# FMC_Test_Module.net
KiCad netlist of a schematic drawn in Altium Designer
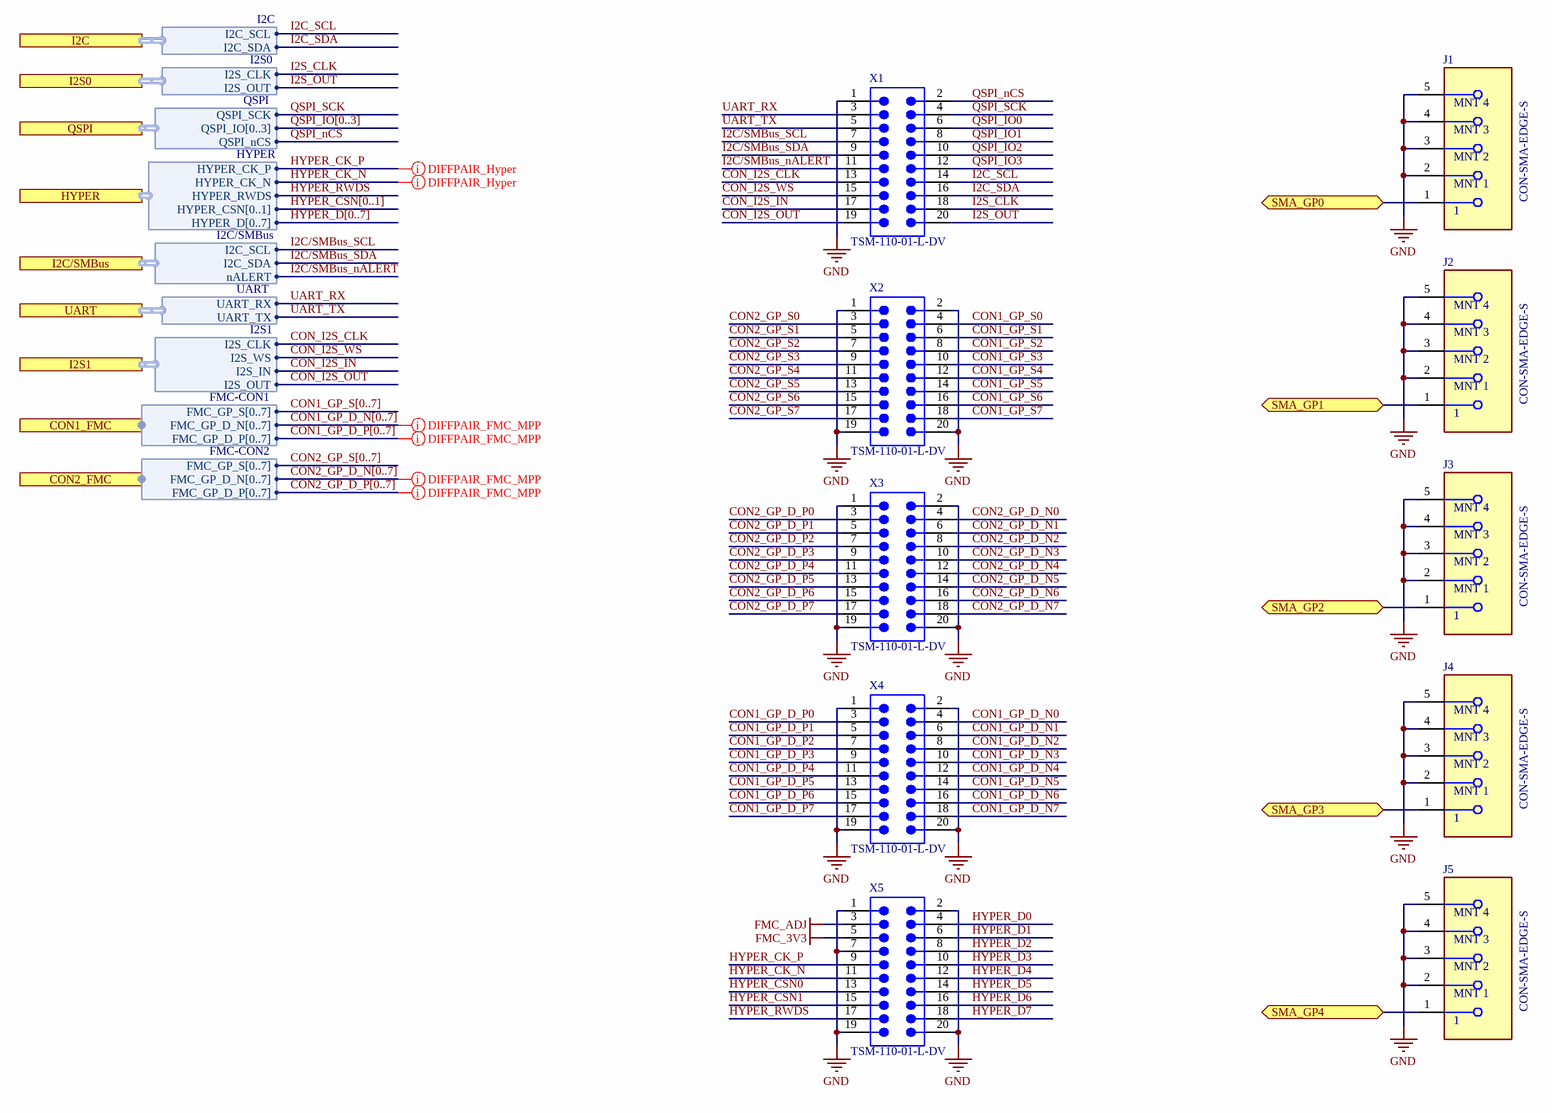
[diagram p0: FMC_Test_Module.SchDoc]

(export (version "E")
  (design (tool "Eeschema 10.0.6"))
  (components
    (comp (ref "J1")
      (value "CON-SMA-EDGE-S")
      (footprint "FP-CON-SMA-EDGE-S-MFG")
      (description "CONN SMA JACK STR EDGE MNT")
      (fields
        (field (name "OCTOPART") "https://octopart.com/con-sma-edge-s-rf+solutions-70967450")
        (field (name "MANUFACTURER") "RF Solutions Ltd.")
      )
      (libsource (lib "Altium Content Vault") (part "a163d97a771fcdd2fd1f1a9264c171f"))
    )
    (comp (ref "J2")
      (value "CON-SMA-EDGE-S")
      (footprint "FP-CON-SMA-EDGE-S-MFG")
      (description "CONN SMA JACK STR EDGE MNT")
      (fields
        (field (name "OCTOPART") "https://octopart.com/con-sma-edge-s-rf+solutions-70967450")
        (field (name "MANUFACTURER") "RF Solutions Ltd.")
      )
      (libsource (lib "Altium Content Vault") (part "a163d97a771fcdd2fd1f1a9264c171f"))
    )
    (comp (ref "J3")
      (value "CON-SMA-EDGE-S")
      (footprint "FP-CON-SMA-EDGE-S-MFG")
      (description "CONN SMA JACK STR EDGE MNT")
      (fields
        (field (name "OCTOPART") "https://octopart.com/con-sma-edge-s-rf+solutions-70967450")
        (field (name "MANUFACTURER") "RF Solutions Ltd.")
      )
      (libsource (lib "Altium Content Vault") (part "a163d97a771fcdd2fd1f1a9264c171f"))
    )
    (comp (ref "J4")
      (value "CON-SMA-EDGE-S")
      (footprint "FP-CON-SMA-EDGE-S-MFG")
      (description "CONN SMA JACK STR EDGE MNT")
      (fields
        (field (name "OCTOPART") "https://octopart.com/con-sma-edge-s-rf+solutions-70967450")
        (field (name "MANUFACTURER") "RF Solutions Ltd.")
      )
      (libsource (lib "Altium Content Vault") (part "a163d97a771fcdd2fd1f1a9264c171f"))
    )
    (comp (ref "J5")
      (value "CON-SMA-EDGE-S")
      (footprint "FP-CON-SMA-EDGE-S-MFG")
      (description "CONN SMA JACK STR EDGE MNT")
      (fields
        (field (name "OCTOPART") "https://octopart.com/con-sma-edge-s-rf+solutions-70967450")
        (field (name "MANUFACTURER") "RF Solutions Ltd.")
      )
      (libsource (lib "Altium Content Vault") (part "a163d97a771fcdd2fd1f1a9264c171f"))
    )
    (comp (ref "X1")
      (value "TSM-110-01-L-DV")
      (footprint "SMTC-TSM-110-01-X-DV")
      (fields (field (name "MANUFACTURER") "Samtec"))
      (libsource (lib "Altium Content Vault") (part "SMTC-TSM-110-01-X-DV"))
    )
    (comp (ref "X2")
      (value "TSM-110-01-L-DV")
      (footprint "SMTC-TSM-110-01-X-DV")
      (fields (field (name "MANUFACTURER") "Samtec"))
      (libsource (lib "Altium Content Vault") (part "SMTC-TSM-110-01-X-DV"))
    )
    (comp (ref "X3")
      (value "TSM-110-01-L-DV")
      (footprint "SMTC-TSM-110-01-X-DV")
      (fields (field (name "MANUFACTURER") "Samtec"))
      (libsource (lib "Altium Content Vault") (part "SMTC-TSM-110-01-X-DV"))
    )
    (comp (ref "X4")
      (value "TSM-110-01-L-DV")
      (footprint "SMTC-TSM-110-01-X-DV")
      (fields (field (name "MANUFACTURER") "Samtec"))
      (libsource (lib "Altium Content Vault") (part "SMTC-TSM-110-01-X-DV"))
    )
    (comp (ref "X5")
      (value "TSM-110-01-L-DV")
      (footprint "SMTC-TSM-110-01-X-DV")
      (fields (field (name "MANUFACTURER") "Samtec"))
      (libsource (lib "Altium Content Vault") (part "SMTC-TSM-110-01-X-DV"))
    )
  )
  (nets
    (net (code "11") (name "/CON1_GP_D_N0") (class "Default")
      (node (ref "X4") (pin "4") (pinfunction "4_4") (pintype "passive"))
    )
    (net (code "12") (name "/CON1_GP_D_N1") (class "Default")
      (node (ref "X4") (pin "6") (pinfunction "6_6") (pintype "passive"))
    )
    (net (code "13") (name "/CON1_GP_D_N2") (class "Default")
      (node (ref "X4") (pin "8") (pinfunction "8_8") (pintype "passive"))
    )
    (net (code "14") (name "/CON1_GP_D_N3") (class "Default")
      (node (ref "X4") (pin "10") (pinfunction "10_10") (pintype "passive"))
    )
    (net (code "15") (name "/CON1_GP_D_N4") (class "Default")
      (node (ref "X4") (pin "12") (pinfunction "12_12") (pintype "passive"))
    )
    (net (code "16") (name "/CON1_GP_D_N5") (class "Default")
      (node (ref "X4") (pin "14") (pinfunction "14_14") (pintype "passive"))
    )
    (net (code "17") (name "/CON1_GP_D_N6") (class "Default")
      (node (ref "X4") (pin "16") (pinfunction "16_16") (pintype "passive"))
    )
    (net (code "18") (name "/CON1_GP_D_N7") (class "Default")
      (node (ref "X4") (pin "18") (pinfunction "18_18") (pintype "passive"))
    )
    (net (code "20") (name "/CON1_GP_D_P0") (class "Default")
      (node (ref "X4") (pin "3") (pinfunction "3_3") (pintype "passive"))
    )
    (net (code "21") (name "/CON1_GP_D_P1") (class "Default")
      (node (ref "X4") (pin "5") (pinfunction "5_5") (pintype "passive"))
    )
    (net (code "22") (name "/CON1_GP_D_P2") (class "Default")
      (node (ref "X4") (pin "7") (pinfunction "7_7") (pintype "passive"))
    )
    (net (code "23") (name "/CON1_GP_D_P3") (class "Default")
      (node (ref "X4") (pin "9") (pinfunction "9_9") (pintype "passive"))
    )
    (net (code "24") (name "/CON1_GP_D_P4") (class "Default")
      (node (ref "X4") (pin "11") (pinfunction "11_11") (pintype "passive"))
    )
    (net (code "25") (name "/CON1_GP_D_P5") (class "Default")
      (node (ref "X4") (pin "13") (pinfunction "13_13") (pintype "passive"))
    )
    (net (code "26") (name "/CON1_GP_D_P6") (class "Default")
      (node (ref "X4") (pin "15") (pinfunction "15_15") (pintype "passive"))
    )
    (net (code "27") (name "/CON1_GP_D_P7") (class "Default")
      (node (ref "X4") (pin "17") (pinfunction "17_17") (pintype "passive"))
    )
    (net (code "29") (name "/CON1_GP_S0") (class "Default")
      (node (ref "X2") (pin "4") (pinfunction "4_4") (pintype "passive"))
    )
    (net (code "30") (name "/CON1_GP_S1") (class "Default")
      (node (ref "X2") (pin "6") (pinfunction "6_6") (pintype "passive"))
    )
    (net (code "31") (name "/CON1_GP_S2") (class "Default")
      (node (ref "X2") (pin "8") (pinfunction "8_8") (pintype "passive"))
    )
    (net (code "32") (name "/CON1_GP_S3") (class "Default")
      (node (ref "X2") (pin "10") (pinfunction "10_10") (pintype "passive"))
    )
    (net (code "33") (name "/CON1_GP_S4") (class "Default")
      (node (ref "X2") (pin "12") (pinfunction "12_12") (pintype "passive"))
    )
    (net (code "34") (name "/CON1_GP_S5") (class "Default")
      (node (ref "X2") (pin "14") (pinfunction "14_14") (pintype "passive"))
    )
    (net (code "35") (name "/CON1_GP_S6") (class "Default")
      (node (ref "X2") (pin "16") (pinfunction "16_16") (pintype "passive"))
    )
    (net (code "36") (name "/CON1_GP_S7") (class "Default")
      (node (ref "X2") (pin "18") (pinfunction "18_18") (pintype "passive"))
    )
    (net (code "38") (name "/CON2_GP_D_N0") (class "Default")
      (node (ref "X3") (pin "4") (pinfunction "4_4") (pintype "passive"))
    )
    (net (code "39") (name "/CON2_GP_D_N1") (class "Default")
      (node (ref "X3") (pin "6") (pinfunction "6_6") (pintype "passive"))
    )
    (net (code "40") (name "/CON2_GP_D_N2") (class "Default")
      (node (ref "X3") (pin "8") (pinfunction "8_8") (pintype "passive"))
    )
    (net (code "41") (name "/CON2_GP_D_N3") (class "Default")
      (node (ref "X3") (pin "10") (pinfunction "10_10") (pintype "passive"))
    )
    (net (code "42") (name "/CON2_GP_D_N4") (class "Default")
      (node (ref "X3") (pin "12") (pinfunction "12_12") (pintype "passive"))
    )
    (net (code "43") (name "/CON2_GP_D_N5") (class "Default")
      (node (ref "X3") (pin "14") (pinfunction "14_14") (pintype "passive"))
    )
    (net (code "44") (name "/CON2_GP_D_N6") (class "Default")
      (node (ref "X3") (pin "16") (pinfunction "16_16") (pintype "passive"))
    )
    (net (code "45") (name "/CON2_GP_D_N7") (class "Default")
      (node (ref "X3") (pin "18") (pinfunction "18_18") (pintype "passive"))
    )
    (net (code "47") (name "/CON2_GP_D_P0") (class "Default")
      (node (ref "X3") (pin "3") (pinfunction "3_3") (pintype "passive"))
    )
    (net (code "48") (name "/CON2_GP_D_P1") (class "Default")
      (node (ref "X3") (pin "5") (pinfunction "5_5") (pintype "passive"))
    )
    (net (code "49") (name "/CON2_GP_D_P2") (class "Default")
      (node (ref "X3") (pin "7") (pinfunction "7_7") (pintype "passive"))
    )
    (net (code "50") (name "/CON2_GP_D_P3") (class "Default")
      (node (ref "X3") (pin "9") (pinfunction "9_9") (pintype "passive"))
    )
    (net (code "51") (name "/CON2_GP_D_P4") (class "Default")
      (node (ref "X3") (pin "11") (pinfunction "11_11") (pintype "passive"))
    )
    (net (code "52") (name "/CON2_GP_D_P5") (class "Default")
      (node (ref "X3") (pin "13") (pinfunction "13_13") (pintype "passive"))
    )
    (net (code "53") (name "/CON2_GP_D_P6") (class "Default")
      (node (ref "X3") (pin "15") (pinfunction "15_15") (pintype "passive"))
    )
    (net (code "54") (name "/CON2_GP_D_P7") (class "Default")
      (node (ref "X3") (pin "17") (pinfunction "17_17") (pintype "passive"))
    )
    (net (code "55") (name "/CON2_GP_S0") (class "Default")
      (node (ref "X2") (pin "3") (pinfunction "3_3") (pintype "passive"))
    )
    (net (code "56") (name "/CON2_GP_S1") (class "Default")
      (node (ref "X2") (pin "5") (pinfunction "5_5") (pintype "passive"))
    )
    (net (code "57") (name "/CON2_GP_S2") (class "Default")
      (node (ref "X2") (pin "7") (pinfunction "7_7") (pintype "passive"))
    )
    (net (code "58") (name "/CON2_GP_S3") (class "Default")
      (node (ref "X2") (pin "9") (pinfunction "9_9") (pintype "passive"))
    )
    (net (code "59") (name "/CON2_GP_S4") (class "Default")
      (node (ref "X2") (pin "11") (pinfunction "11_11") (pintype "passive"))
    )
    (net (code "60") (name "/CON2_GP_S5") (class "Default")
      (node (ref "X2") (pin "13") (pinfunction "13_13") (pintype "passive"))
    )
    (net (code "61") (name "/CON2_GP_S6") (class "Default")
      (node (ref "X2") (pin "15") (pinfunction "15_15") (pintype "passive"))
    )
    (net (code "62") (name "/CON2_GP_S7") (class "Default")
      (node (ref "X2") (pin "17") (pinfunction "17_17") (pintype "passive"))
    )
    (net (code "64") (name "/CON_I2S_CLK") (class "Default")
      (node (ref "X1") (pin "13") (pinfunction "13_13") (pintype "passive"))
    )
    (net (code "65") (name "/CON_I2S_IN") (class "Default")
      (node (ref "X1") (pin "17") (pinfunction "17_17") (pintype "passive"))
    )
    (net (code "66") (name "/CON_I2S_OUT") (class "Default")
      (node (ref "X1") (pin "19") (pinfunction "19_19") (pintype "passive"))
    )
    (net (code "67") (name "/CON_I2S_WS") (class "Default")
      (node (ref "X1") (pin "15") (pinfunction "15_15") (pintype "passive"))
    )
    (net (code "68") (name "/HYPER_CK_N") (class "Default")
      (node (ref "X5") (pin "11") (pinfunction "11_11") (pintype "passive"))
    )
    (net (code "69") (name "/HYPER_CK_P") (class "Default")
      (node (ref "X5") (pin "9") (pinfunction "9_9") (pintype "passive"))
    )
    (net (code "70") (name "/HYPER_CSN0") (class "Default")
      (node (ref "X5") (pin "13") (pinfunction "13_13") (pintype "passive"))
    )
    (net (code "71") (name "/HYPER_CSN1") (class "Default")
      (node (ref "X5") (pin "15") (pinfunction "15_15") (pintype "passive"))
    )
    (net (code "73") (name "/HYPER_D0") (class "Default")
      (node (ref "X5") (pin "4") (pinfunction "4_4") (pintype "passive"))
    )
    (net (code "74") (name "/HYPER_D1") (class "Default")
      (node (ref "X5") (pin "6") (pinfunction "6_6") (pintype "passive"))
    )
    (net (code "75") (name "/HYPER_D2") (class "Default")
      (node (ref "X5") (pin "8") (pinfunction "8_8") (pintype "passive"))
    )
    (net (code "76") (name "/HYPER_D3") (class "Default")
      (node (ref "X5") (pin "10") (pinfunction "10_10") (pintype "passive"))
    )
    (net (code "77") (name "/HYPER_D4") (class "Default")
      (node (ref "X5") (pin "12") (pinfunction "12_12") (pintype "passive"))
    )
    (net (code "78") (name "/HYPER_D5") (class "Default")
      (node (ref "X5") (pin "14") (pinfunction "14_14") (pintype "passive"))
    )
    (net (code "79") (name "/HYPER_D6") (class "Default")
      (node (ref "X5") (pin "16") (pinfunction "16_16") (pintype "passive"))
    )
    (net (code "80") (name "/HYPER_D7") (class "Default")
      (node (ref "X5") (pin "18") (pinfunction "18_18") (pintype "passive"))
    )
    (net (code "82") (name "/HYPER_RWDS") (class "Default")
      (node (ref "X5") (pin "17") (pinfunction "17_17") (pintype "passive"))
    )
    (net (code "83") (name "/I2C_SCL") (class "Default")
      (node (ref "X1") (pin "14") (pinfunction "14_14") (pintype "passive"))
    )
    (net (code "84") (name "/I2C_SDA") (class "Default")
      (node (ref "X1") (pin "16") (pinfunction "16_16") (pintype "passive"))
    )
    (net (code "85") (name "/I2C{slash}SMBus_SCL") (class "Default")
      (node (ref "X1") (pin "7") (pinfunction "7_7") (pintype "passive"))
    )
    (net (code "86") (name "/I2C{slash}SMBus_SDA") (class "Default")
      (node (ref "X1") (pin "9") (pinfunction "9_9") (pintype "passive"))
    )
    (net (code "87") (name "/I2C{slash}SMBus_nALERT") (class "Default")
      (node (ref "X1") (pin "11") (pinfunction "11_11") (pintype "passive"))
    )
    (net (code "88") (name "/I2S_CLK") (class "Default")
      (node (ref "X1") (pin "18") (pinfunction "18_18") (pintype "passive"))
    )
    (net (code "89") (name "/I2S_OUT") (class "Default")
      (node (ref "X1") (pin "20") (pinfunction "20_20") (pintype "passive"))
    )
    (net (code "90") (name "/QSPI_IO0") (class "Default")
      (node (ref "X1") (pin "6") (pinfunction "6_6") (pintype "passive"))
    )
    (net (code "91") (name "/QSPI_IO1") (class "Default")
      (node (ref "X1") (pin "8") (pinfunction "8_8") (pintype "passive"))
    )
    (net (code "92") (name "/QSPI_IO2") (class "Default")
      (node (ref "X1") (pin "10") (pinfunction "10_10") (pintype "passive"))
    )
    (net (code "93") (name "/QSPI_IO3") (class "Default")
      (node (ref "X1") (pin "12") (pinfunction "12_12") (pintype "passive"))
    )
    (net (code "95") (name "/QSPI_SCK") (class "Default")
      (node (ref "X1") (pin "4") (pinfunction "4_4") (pintype "passive"))
    )
    (net (code "96") (name "/QSPI_nCS") (class "Default")
      (node (ref "X1") (pin "2") (pinfunction "2_2") (pintype "passive"))
    )
    (net (code "97") (name "/SMA_GP0") (class "Default")
      (node (ref "J1") (pin "1") (pinfunction "1_1") (pintype "passive"))
    )
    (net (code "98") (name "/SMA_GP1") (class "Default")
      (node (ref "J2") (pin "1") (pinfunction "1_1") (pintype "passive"))
    )
    (net (code "99") (name "/SMA_GP2") (class "Default")
      (node (ref "J3") (pin "1") (pinfunction "1_1") (pintype "passive"))
    )
    (net (code "100") (name "/SMA_GP3") (class "Default")
      (node (ref "J4") (pin "1") (pinfunction "1_1") (pintype "passive"))
    )
    (net (code "101") (name "/SMA_GP4") (class "Default")
      (node (ref "J5") (pin "1") (pinfunction "1_1") (pintype "passive"))
    )
    (net (code "102") (name "/UART_RX") (class "Default")
      (node (ref "X1") (pin "3") (pinfunction "3_3") (pintype "passive"))
    )
    (net (code "103") (name "/UART_TX") (class "Default")
      (node (ref "X1") (pin "5") (pinfunction "5_5") (pintype "passive"))
    )
    (net (code "111") (name "FMC_3V3") (class "Default")
      (node (ref "X5") (pin "5") (pinfunction "5_5") (pintype "passive"))
    )
    (net (code "112") (name "FMC_ADJ") (class "Default")
      (node (ref "X5") (pin "3") (pinfunction "3_3") (pintype "passive"))
    )
    (net (code "113") (name "GND") (class "Default")
      (node (ref "J1") (pin "2") (pinfunction "MNT_1_2") (pintype "passive"))
      (node (ref "J1") (pin "3") (pinfunction "MNT_2_3") (pintype "passive"))
      (node (ref "J1") (pin "4") (pinfunction "MNT_3_4") (pintype "passive"))
      (node (ref "J1") (pin "5") (pinfunction "MNT_4_5") (pintype "passive"))
      (node (ref "J2") (pin "2") (pinfunction "MNT_1_2") (pintype "passive"))
      (node (ref "J2") (pin "3") (pinfunction "MNT_2_3") (pintype "passive"))
      (node (ref "J2") (pin "4") (pinfunction "MNT_3_4") (pintype "passive"))
      (node (ref "J2") (pin "5") (pinfunction "MNT_4_5") (pintype "passive"))
      (node (ref "J3") (pin "2") (pinfunction "MNT_1_2") (pintype "passive"))
      (node (ref "J3") (pin "3") (pinfunction "MNT_2_3") (pintype "passive"))
      (node (ref "J3") (pin "4") (pinfunction "MNT_3_4") (pintype "passive"))
      (node (ref "J3") (pin "5") (pinfunction "MNT_4_5") (pintype "passive"))
      (node (ref "J4") (pin "2") (pinfunction "MNT_1_2") (pintype "passive"))
      (node (ref "J4") (pin "3") (pinfunction "MNT_2_3") (pintype "passive"))
      (node (ref "J4") (pin "4") (pinfunction "MNT_3_4") (pintype "passive"))
      (node (ref "J4") (pin "5") (pinfunction "MNT_4_5") (pintype "passive"))
      (node (ref "J5") (pin "2") (pinfunction "MNT_1_2") (pintype "passive"))
      (node (ref "J5") (pin "3") (pinfunction "MNT_2_3") (pintype "passive"))
      (node (ref "J5") (pin "4") (pinfunction "MNT_3_4") (pintype "passive"))
      (node (ref "J5") (pin "5") (pinfunction "MNT_4_5") (pintype "passive"))
      (node (ref "X1") (pin "1") (pinfunction "1_1") (pintype "passive"))
      (node (ref "X2") (pin "1") (pinfunction "1_1") (pintype "passive"))
      (node (ref "X2") (pin "19") (pinfunction "19_19") (pintype "passive"))
      (node (ref "X2") (pin "2") (pinfunction "2_2") (pintype "passive"))
      (node (ref "X2") (pin "20") (pinfunction "20_20") (pintype "passive"))
      (node (ref "X3") (pin "1") (pinfunction "1_1") (pintype "passive"))
      (node (ref "X3") (pin "19") (pinfunction "19_19") (pintype "passive"))
      (node (ref "X3") (pin "2") (pinfunction "2_2") (pintype "passive"))
      (node (ref "X3") (pin "20") (pinfunction "20_20") (pintype "passive"))
      (node (ref "X4") (pin "1") (pinfunction "1_1") (pintype "passive"))
      (node (ref "X4") (pin "19") (pinfunction "19_19") (pintype "passive"))
      (node (ref "X4") (pin "2") (pinfunction "2_2") (pintype "passive"))
      (node (ref "X4") (pin "20") (pinfunction "20_20") (pintype "passive"))
      (node (ref "X5") (pin "1") (pinfunction "1_1") (pintype "passive"))
      (node (ref "X5") (pin "19") (pinfunction "19_19") (pintype "passive"))
      (node (ref "X5") (pin "2") (pinfunction "2_2") (pintype "passive"))
      (node (ref "X5") (pin "20") (pinfunction "20_20") (pintype "passive"))
      (node (ref "X5") (pin "7") (pinfunction "7_7") (pintype "passive"))
    )
  )
)
